# power.net
KiCad netlist of a schematic drawn in Altium Designer
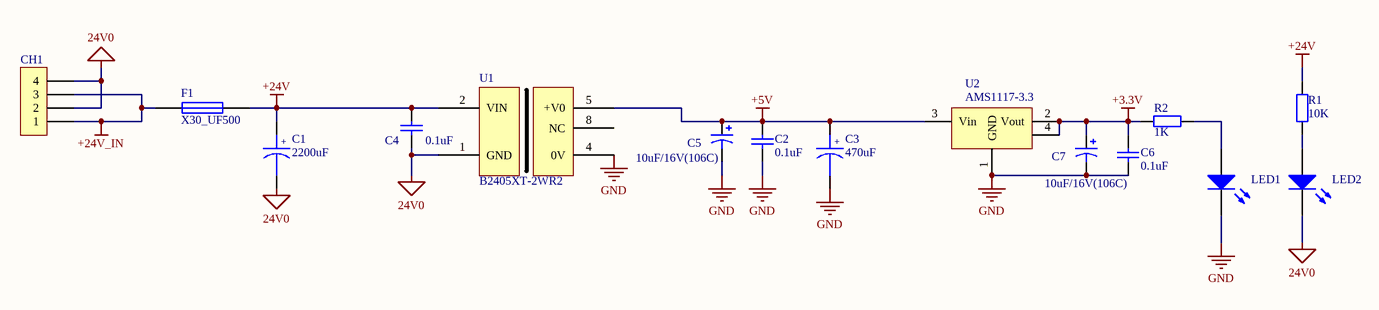
[diagram p0: power.SchDoc]

(export (version "E")
  (design (tool "Eeschema 10.0.6"))
  (components
    (comp (ref "C1")
      (value "C_2200uF")
      (footprint "C7.8*17")
      (fields (field (name "ALTIUM_UNNAMED_1") "2200uF"))
      (libsource (lib "myIntegrated_Library1") (part "C_2200uF"))
    )
    (comp (ref "C2")
      (value "0.1uF")
      (footprint "0805")
      (description "Capacitor")
      (fields (field (name "Comment") "Cap") (field (name "PUBLISHER") "Altium Limited"))
      (libsource (lib "Miscellaneous Devices") (part "Cap"))
    )
    (comp (ref "C3")
      (value "C_2200uF")
      (footprint "C5*10")
      (fields (field (name "ALTIUM_UNNAMED_1") "470uF"))
      (libsource (lib "myIntegrated_Library1") (part "C_2200uF"))
    )
    (comp (ref "C4")
      (value "0.1uF")
      (footprint "0805")
      (description "Capacitor")
      (fields (field (name "Comment") "Cap") (field (name "PUBLISHER") "Altium Limited"))
      (libsource (lib "Miscellaneous Devices") (part "Cap"))
    )
    (comp (ref "C5")
      (value "10uF/16V(106C)")
      (footprint "CAP A-3216")
      (description "Polarized Capacitor (Surface Mount)")
      (fields (field (name "Comment") "Cap Pol3") (field (name "PUBLISHER") "Altium Limited"))
      (libsource (lib "Miscellaneous Devices") (part "Cap Pol3"))
    )
    (comp (ref "C6")
      (value "0.1uF")
      (footprint "0805")
      (description "Capacitor")
      (fields (field (name "Comment") "Cap") (field (name "PUBLISHER") "Altium Limited"))
      (libsource (lib "Miscellaneous Devices") (part "Cap"))
    )
    (comp (ref "C7")
      (value "10uF/16V(106C)")
      (footprint "CAP A-3216")
      (description "Polarized Capacitor (Surface Mount)")
      (fields (field (name "Comment") "Cap Pol3") (field (name "PUBLISHER") "Altium Limited"))
      (libsource (lib "Miscellaneous Devices") (part "Cap Pol3"))
    )
    (comp (ref "CH1")
      (value "HEADER1X4")
      (footprint "CH3.96-4PIN")
      (libsource (lib "myIntegrated_Library1") (part "HEADER1X4"))
    )
    (comp (ref "F1")
      (value "X30_UF500")
      (footprint "X30UF600")
      (description "Fuse")
      (fields (field (name "PUBLISHER") "Altium Limited"))
      (libsource (lib "Miscellaneous Devices") (part "Fuse 1"))
    )
    (comp (ref "LED1")
      (value "~")
      (footprint "LED-0805")
      (description "Typical RED, GREEN, YELLOW, AMBER GaAs LED")
      (fields (field (name "PUBLISHER") "Altium Limited"))
      (libsource (lib "Miscellaneous Devices") (part "LED2"))
    )
    (comp (ref "LED2")
      (value "~")
      (footprint "LED-0805")
      (description "Typical RED, GREEN, YELLOW, AMBER GaAs LED")
      (fields (field (name "PUBLISHER") "Altium Limited"))
      (libsource (lib "Miscellaneous Devices") (part "LED2"))
    )
    (comp (ref "R1")
      (value "10K")
      (footprint "0805")
      (description "Resistor")
      (fields (field (name "Comment") "Res2") (field (name "PUBLISHER") "Altium Limited"))
      (libsource (lib "") (part "Res2_1"))
    )
    (comp (ref "R2")
      (value "1K")
      (footprint "0805")
      (description "Resistor")
      (fields (field (name "Comment") "Res2") (field (name "PUBLISHER") "Altium Limited"))
      (libsource (lib "Miscellaneous Devices") (part "Res2"))
    )
    (comp (ref "U1")
      (value "B2405XT-2WR2")
      (footprint "B2405XT-2WR2")
      (libsource (lib "myIntegrated_Library1") (part "B2405XT-2WR2"))
    )
    (comp (ref "U2")
      (value "AMS1117-3.3")
      (footprint "SOT223")
      (libsource (lib "货架电子标签元件库") (part "AMS1117-5"))
    )
  )
  (nets
    (net (code "1") (name "+3.3V") (class "Default")
      (node (ref "C6") (pin "2") (pinfunction "2_2") (pintype "passive"))
      (node (ref "C7") (pin "1") (pinfunction "1_1") (pintype "passive"))
      (node (ref "R2") (pin "2") (pinfunction "2_2") (pintype "passive"))
      (node (ref "U2") (pin "2") (pinfunction "Vout_2") (pintype "passive"))
      (node (ref "U2") (pin "4") (pintype "passive"))
    )
    (net (code "2") (name "+5V") (class "Default")
      (node (ref "C2") (pin "2") (pinfunction "2_2") (pintype "passive"))
      (node (ref "C3") (pin "1") (pinfunction "1_1") (pintype "passive"))
      (node (ref "C5") (pin "1") (pinfunction "1_1") (pintype "passive"))
      (node (ref "U1") (pin "5") (pinfunction "+V0_5") (pintype "passive"))
      (node (ref "U2") (pin "3") (pinfunction "Vin_3") (pintype "passive"))
    )
    (net (code "3") (name "+24V") (class "Default")
      (node (ref "C1") (pin "1") (pinfunction "1_1") (pintype "passive"))
      (node (ref "C4") (pin "2") (pinfunction "2_2") (pintype "passive"))
      (node (ref "F1") (pin "2") (pinfunction "2_2") (pintype "passive"))
      (node (ref "R1") (pin "2") (pinfunction "2_2") (pintype "passive"))
      (node (ref "U1") (pin "2") (pinfunction "VIN_2") (pintype "passive"))
    )
    (net (code "4") (name "+24V_IN") (class "Default")
      (node (ref "CH1") (pin "1") (pinfunction "1_1") (pintype "passive"))
      (node (ref "CH1") (pin "3") (pinfunction "3_3") (pintype "passive"))
      (node (ref "F1") (pin "1") (pinfunction "1_1") (pintype "passive"))
    )
    (net (code "5") (name "24V0") (class "Default")
      (node (ref "C1") (pin "2") (pinfunction "2_2") (pintype "passive"))
      (node (ref "C4") (pin "1") (pinfunction "1_1") (pintype "passive"))
      (node (ref "CH1") (pin "2") (pinfunction "2_2") (pintype "passive"))
      (node (ref "CH1") (pin "4") (pinfunction "4_4") (pintype "passive"))
      (node (ref "LED2") (pin "2") (pinfunction "K_2") (pintype "passive"))
      (node (ref "U1") (pin "1") (pinfunction "GND_1") (pintype "passive"))
    )
    (net (code "6") (name "GND") (class "Default")
      (node (ref "C2") (pin "1") (pinfunction "1_1") (pintype "passive"))
      (node (ref "C3") (pin "2") (pinfunction "2_2") (pintype "passive"))
      (node (ref "C5") (pin "2") (pinfunction "2_2") (pintype "passive"))
      (node (ref "C6") (pin "1") (pinfunction "1_1") (pintype "passive"))
      (node (ref "C7") (pin "2") (pinfunction "2_2") (pintype "passive"))
      (node (ref "LED1") (pin "2") (pinfunction "K_2") (pintype "passive"))
      (node (ref "U1") (pin "4") (pinfunction "0V_4") (pintype "passive"))
      (node (ref "U2") (pin "1") (pinfunction "GND_1") (pintype "passive"))
    )
    (net (code "7") (name "Net-(LED1-A)") (class "Default")
      (node (ref "LED1") (pin "1") (pinfunction "A_1") (pintype "passive"))
      (node (ref "R2") (pin "1") (pinfunction "1_1") (pintype "passive"))
    )
    (net (code "8") (name "Net-(LED2-A)") (class "Default")
      (node (ref "LED2") (pin "1") (pinfunction "A_1") (pintype "passive"))
      (node (ref "R1") (pin "1") (pinfunction "1_1") (pintype "passive"))
    )
    (net (code "9") (name "unconnected-(U1-NC-Pad8)") (class "Default")
      (node (ref "U1") (pin "8") (pinfunction "NC_8") (pintype "passive"))
    )
  )
)
